# TIDA-010954-ACSwitch.net
KiCad netlist of a schematic drawn in Altium Designer
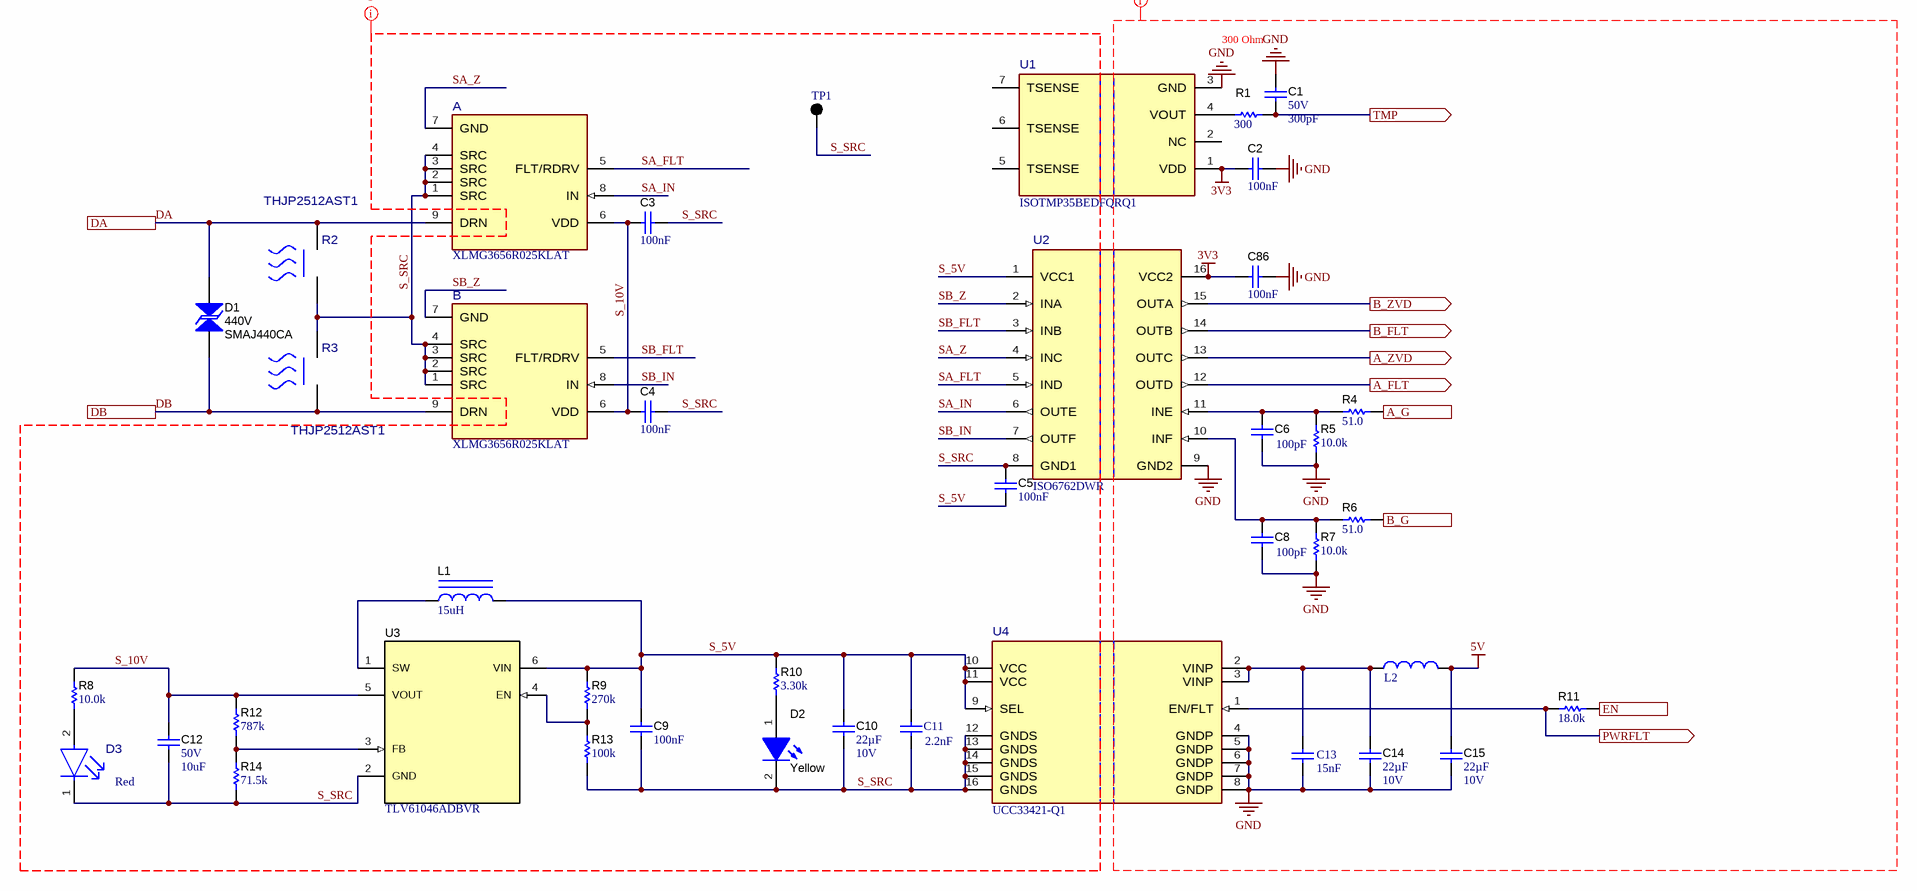
[diagram p0: TIDA-010954-ACSwitch.SchDoc]

(export (version "E")
  (design (tool "Eeschema 10.0.6"))
  (components
    (comp (ref "A")
      (value "XLMG3656R025KLAT")
      (footprint "KLA0009A-MFG")
      (fields
        (field (name "MANUFACTURER") "Texas Instruments")
        (field (name "PARTNUMBER") "XLMG3656R025KLAT")
        (field (name "PART NUMBER") "LMG365x")
      )
      (libsource (lib "Altium Vault - TI") (part "SYM-LMG365x"))
    )
    (comp (ref "B")
      (value "XLMG3656R025KLAT")
      (footprint "KLA0009A-MFG")
      (fields
        (field (name "MANUFACTURER") "Texas Instruments")
        (field (name "PARTNUMBER") "XLMG3656R025KLAT")
        (field (name "PART NUMBER") "LMG365x")
      )
      (libsource (lib "Altium Vault - TI") (part "SYM-LMG365x"))
    )
    (comp (ref "C1")
      (value "GRM1885C1H301JA01D")
      (footprint "0603")
      (description "CAP, CERM, 300 pF, 50 V, +/- 5%, C0G/NP0, 0603")
      (fields
        (field (name "MANUFACTURER") "MuRata")
        (field (name "VDC_V") "50V")
        (field (name "VALUEDISPLAYED") "300pF")
        (field (name "PUBLISHER") "Texas Instruments")
      )
      (libsource (lib "Altium Vault - TI") (part "Capacitor"))
    )
    (comp (ref "C2")
      (value "CGA3E2X7R1E104K080AA")
      (footprint "0603")
      (description "CAP, CERM, 0.1 uF, 25 V, +/- 10%, X7R, AEC-Q200 Grade 1, 0603")
      (fields
        (field (name "MANUFACTURER") "TDK")
        (field (name "CAP_F") "100nF")
        (field (name "PUBLISHER") "Texas Instruments")
      )
      (libsource (lib "Altium Vault - TI") (part "Capacitor"))
    )
    (comp (ref "C3")
      (value "CGA3E2X7R1E104K080AA")
      (footprint "0603")
      (description "CAP, CERM, 0.1 uF, 25 V, +/- 10%, X7R, AEC-Q200 Grade 1, 0603")
      (fields
        (field (name "MANUFACTURER") "TDK")
        (field (name "CAP_F") "100nF")
        (field (name "PUBLISHER") "Texas Instruments")
      )
      (libsource (lib "Altium Vault - TI") (part "Capacitor"))
    )
    (comp (ref "C4")
      (value "CGA3E2X7R1E104K080AA")
      (footprint "0603")
      (description "CAP, CERM, 0.1 uF, 25 V, +/- 10%, X7R, AEC-Q200 Grade 1, 0603")
      (fields
        (field (name "MANUFACTURER") "TDK")
        (field (name "CAP_F") "100nF")
        (field (name "PUBLISHER") "Texas Instruments")
      )
      (libsource (lib "Altium Vault - TI") (part "Capacitor"))
    )
    (comp (ref "C5")
      (value "CGA3E2X7R1E104K080AA")
      (footprint "0603")
      (description "CAP, CERM, 0.1 uF, 25 V, +/- 10%, X7R, AEC-Q200 Grade 1, 0603")
      (fields
        (field (name "MANUFACTURER") "TDK")
        (field (name "CAP_F") "100nF")
        (field (name "PUBLISHER") "Texas Instruments")
      )
      (libsource (lib "Altium Vault - TI") (part "Capacitor"))
    )
    (comp (ref "C6")
      (value "GRM1885C1H101JA01D")
      (footprint "0603")
      (description "CAP, CERM, 100 pF, 50 V, +/- 5%, C0G/NP0, 0603")
      (fields
        (field (name "MANUFACTURER") "MuRata")
        (field (name "VALUEDISPLAYED") "100pF")
        (field (name "PUBLISHER") "Texas Instruments")
      )
      (libsource (lib "Altium Vault - TI") (part "Capacitor"))
    )
    (comp (ref "C8")
      (value "GRM1885C1H101JA01D")
      (footprint "0603")
      (description "CAP, CERM, 100 pF, 50 V, +/- 5%, C0G/NP0, 0603")
      (fields
        (field (name "MANUFACTURER") "MuRata")
        (field (name "VALUEDISPLAYED") "100pF")
        (field (name "PUBLISHER") "Texas Instruments")
      )
      (libsource (lib "Altium Vault - TI") (part "Capacitor"))
    )
    (comp (ref "C9")
      (value "CGA3E2X7R1E104K080AA")
      (footprint "0603")
      (description "CAP, CERM, 0.1 uF, 25 V, +/- 10%, X7R, AEC-Q200 Grade 1, 0603")
      (fields
        (field (name "MANUFACTURER") "TDK")
        (field (name "CAP_F") "100nF")
        (field (name "PUBLISHER") "Texas Instruments")
      )
      (libsource (lib "Altium Vault - TI") (part "Capacitor"))
    )
    (comp (ref "C10")
      (value "GRM21BZ71A226ME15L")
      (footprint "0805_HV")
      (description "CAP, CERM, 22 uF, 10 V, +/- 20%, X7R, 0805")
      (fields
        (field (name "CAP_F") "22µF")
        (field (name "VDC_V") "10V")
        (field (name "MANUFACTURER") "MuRata")
        (field (name "PUBLISHER") "Texas Instruments")
      )
      (libsource (lib "Altium Vault - TI") (part "Capacitor"))
    )
    (comp (ref "C11")
      (value "885012205063")
      (footprint "WCAP-CSGP_0402_L1W0.5H0.5")
      (description "WCAP-CSGP Multilayer Ceramic Chip Capacitor, General Purpose, size 0402, X7R, 2.2nF, 50VDC")
      (fields (field (name "CAP_F") "2.2nF") (field (name "MANUFACTURER") "Wurth Elektronik"))
      (libsource (lib "Altium Vault - TI") (part "8853622110151"))
    )
    (comp (ref "C12")
      (value "GRT31CR61H106KE01L")
      (footprint "1206_180")
      (description "CAP, CERM, 10 uF, 50 V, +/- 10%, X5R, AEC-Q200 Grade 1, 1206")
      (fields
        (field (name "MANUFACTURER") "MuRata")
        (field (name "VDC_V") "50V")
        (field (name "VALUEDISPLAYED") "10uF")
        (field (name "PUBLISHER") "Texas Instruments")
      )
      (libsource (lib "Altium Vault - TI") (part "Capacitor"))
    )
    (comp (ref "C13")
      (value "885012205051")
      (footprint "WCAP-CSGP_0402_L1W0.5H0.5")
      (description "WCAP-CSGP Multilayer Ceramic Chip Capacitor, General Purpose, size 0402, X7R, 15nF, 25VDC")
      (fields (field (name "CAP_F") "15nF") (field (name "MANUFACTURER") "Wurth Elektronik"))
      (libsource (lib "Altium Vault - TI") (part "890764429002CS"))
    )
    (comp (ref "C14")
      (value "GRM21BZ71A226ME15L")
      (footprint "0805_HV")
      (description "CAP, CERM, 22 uF, 10 V, +/- 20%, X7R, 0805")
      (fields
        (field (name "CAP_F") "22µF")
        (field (name "VDC_V") "10V")
        (field (name "MANUFACTURER") "MuRata")
        (field (name "PUBLISHER") "Texas Instruments")
      )
      (libsource (lib "Altium Vault - TI") (part "Capacitor"))
    )
    (comp (ref "C15")
      (value "GRM21BZ71A226ME15L")
      (footprint "0805_HV")
      (description "CAP, CERM, 22 uF, 10 V, +/- 20%, X7R, 0805")
      (fields
        (field (name "CAP_F") "22µF")
        (field (name "VDC_V") "10V")
        (field (name "MANUFACTURER") "MuRata")
        (field (name "PUBLISHER") "Texas Instruments")
      )
      (libsource (lib "Altium Vault - TI") (part "Capacitor"))
    )
    (comp (ref "C86")
      (value "CGA3E2X7R1E104K080AA")
      (footprint "0603")
      (description "CAP, CERM, 0.1 uF, 25 V, +/- 10%, X7R, AEC-Q200 Grade 1, 0603")
      (fields
        (field (name "MANUFACTURER") "TDK")
        (field (name "CAP_F") "100nF")
        (field (name "PUBLISHER") "Texas Instruments")
      )
      (libsource (lib "Altium Vault - TI") (part "Capacitor"))
    )
    (comp (ref "D1")
      (value "SMAJ440CA")
      (footprint "SMA_Bi")
      (description "Diode, TVS, Bi, 440 V, 713 Vc, 400 W, 0.6 A, SMA (non-polarized)")
      (fields (field (name "ALTIUM_VALUE") "440V") (field (name "MANUFACTURER") "Littelfuse"))
      (libsource (lib "Altium Vault - TI") (part "Diode_TVS_Bi"))
    )
    (comp (ref "D2")
      (value "Yellow")
      (footprint "APT1608_Yellow")
      (description "LED, Yellow, SMD")
      (fields (field (name "MANUFACTURER") "Kingbright") (field (name "PARTNUMBER") "APT1608SYCK"))
      (libsource (lib "Altium Vault - TI") (part "LED"))
    )
    (comp (ref "D3")
      (value "APG1608SURKC/T")
      (footprint "FP-APG1608SURKC_T_0603-MFG")
      (description "Red 630nm LED Indication - Discrete 2V 0603 (1608 Metric)")
      (fields
        (field (name "MANUFACTURER") "Kingbright")
        (field (name "MOUSER PART NUMBER") "604-APG1608SURKC/T")
        (field (name "COLOR") "Red")
      )
      (libsource (lib "Altium Vault - TI") (part "SYM-APG1608SURKC_T"))
    )
    (comp (ref "L1")
      (value "SDR0302-150ML")
      (footprint "SDR0302")
      (description "Inductor, Drum Core, Ferrite, 15 uH, 0.65 A, 0.4 ohm, SMD")
      (fields
        (field (name "VALUEDISPLAYED") "15uH")
        (field (name "MANUFACTURER") "Bourns")
        (field (name "PUBLISHER") "Texas Instruments")
      )
      (libsource (lib "Altium Vault - TI") (part "Inductor_Iron"))
    )
    (comp (ref "L2")
      (value "74479763222")
      (footprint "WE-PMI_0603_L1.6W0.8H0.8")
      (description "WE-PMI SMT Power Multilayer Inductor, size 0603, 2.2uH, 0.8A, 375mOhm")
      (fields (field (name "MANUFACTURER") "Wurth Elektronik"))
      (libsource (lib "Altium Vault - TI") (part "74437529203681"))
    )
    (comp (ref "R1")
      (value "RC0603FR-07300RL")
      (footprint "0603")
      (description "RES, 300, 1%, 0.1 W, 0603")
      (fields (field (name "MANUFACTURER") "Yageo") (field (name "VALUEDISPLAYED") "300"))
      (libsource (lib "Altium Vault - TI") (part "Resistor"))
    )
    (comp (ref "R2")
      (value "THJP2512AST1")
      (footprint "FP-THJP2512AST1_2512-MFG")
      (description "Thermal Pad 6.40mm x 3.20mm Rectangular")
      (fields
        (field (name "MANUFACTURER") "Vishay")
        (field (name "DIGIKEY PART NUMBER") "764-THJP2512AST1CT-ND")
      )
      (libsource (lib "Altium Vault - TI") (part "SYM-THJP2512AST1"))
    )
    (comp (ref "R3")
      (value "THJP2512AST1")
      (footprint "FP-THJP2512AST1_2512-MFG")
      (description "Thermal Pad 6.40mm x 3.20mm Rectangular")
      (fields
        (field (name "MANUFACTURER") "Vishay")
        (field (name "DIGIKEY PART NUMBER") "764-THJP2512AST1CT-ND")
      )
      (libsource (lib "Altium Vault - TI") (part "SYM-THJP2512AST1"))
    )
    (comp (ref "R4")
      (value "RC0603FR-0751RL")
      (footprint "0603")
      (description "RES, 51.0, 1%, 0.1 W, 0603")
      (fields (field (name "MANUFACTURER") "Yageo") (field (name "VALUEDISPLAYED") "51.0"))
      (libsource (lib "Altium Vault - TI") (part "Resistor"))
    )
    (comp (ref "R5")
      (value "RC0603FR-0710KL")
      (footprint "0603")
      (description "RES, 10.0 k, 1%, 0.1 W, 0603")
      (fields (field (name "MANUFACTURER") "Yageo") (field (name "VALUEDISPLAYED") "10.0k"))
      (libsource (lib "Altium Vault - TI") (part "Resistor"))
    )
    (comp (ref "R6")
      (value "RC0603FR-0751RL")
      (footprint "0603")
      (description "RES, 51.0, 1%, 0.1 W, 0603")
      (fields (field (name "MANUFACTURER") "Yageo") (field (name "VALUEDISPLAYED") "51.0"))
      (libsource (lib "Altium Vault - TI") (part "Resistor"))
    )
    (comp (ref "R7")
      (value "RC0603FR-0710KL")
      (footprint "0603")
      (description "RES, 10.0 k, 1%, 0.1 W, 0603")
      (fields (field (name "MANUFACTURER") "Yageo") (field (name "VALUEDISPLAYED") "10.0k"))
      (libsource (lib "Altium Vault - TI") (part "Resistor"))
    )
    (comp (ref "R8")
      (value "RC0603FR-0710KL")
      (footprint "0603")
      (description "RES, 10.0 k, 1%, 0.1 W, 0603")
      (fields (field (name "MANUFACTURER") "Yageo") (field (name "VALUEDISPLAYED") "10.0k"))
      (libsource (lib "Altium Vault - TI") (part "Resistor"))
    )
    (comp (ref "R9")
      (value "RC0603FR-07270KL")
      (footprint "0603")
      (description "RES, 270 k, 1%, 0.1 W, 0603")
      (fields (field (name "MANUFACTURER") "Yageo") (field (name "VALUEDISPLAYED") "270k"))
      (libsource (lib "Altium Vault - TI") (part "Resistor"))
    )
    (comp (ref "R10")
      (value "RC0603FR-073K3L")
      (footprint "0603")
      (description "RES, 3.30 k, 1%, 0.1 W, 0603")
      (fields (field (name "VALUEDISPLAYED") "3.30k") (field (name "MANUFACTURER") "Yageo"))
      (libsource (lib "Altium Vault - TI") (part "Resistor"))
    )
    (comp (ref "R11")
      (value "RC0603FR-0718KL")
      (footprint "0603")
      (description "RES, 18.0 k, 1%, 0.1 W, 0603")
      (fields (field (name "MANUFACTURER") "Yageo") (field (name "VALUEDISPLAYED") "18.0k"))
      (libsource (lib "Altium Vault - TI") (part "Resistor"))
    )
    (comp (ref "R12")
      (value "RC0603FR-07787KL")
      (footprint "0603")
      (description "RES, 787 k, 1%, 0.1 W, 0603")
      (fields (field (name "MANUFACTURER") "Yageo") (field (name "VALUEDISPLAYED") "787k"))
      (libsource (lib "Altium Vault - TI") (part "Resistor"))
    )
    (comp (ref "R13")
      (value "RC0603FR-07100KL")
      (footprint "0603")
      (description "RES, 100 k, 1%, 0.1 W, 0603")
      (fields (field (name "MANUFACTURER") "Yageo") (field (name "VALUEDISPLAYED") "100k"))
      (libsource (lib "Altium Vault - TI") (part "Resistor"))
    )
    (comp (ref "R14")
      (value "RC0603FR-0771K5L")
      (footprint "0603")
      (description "RES, 71.5 k, 1%, 0.1 W, 0603")
      (fields (field (name "MANUFACTURER") "Yageo") (field (name "VALUEDISPLAYED") "71.5k"))
      (libsource (lib "Altium Vault - TI") (part "Resistor"))
    )
    (comp (ref "TP1")
      (value "5011")
      (footprint "Keystone5011")
      (description "Test Point, Multipurpose, Black, TH")
      (fields
        (field (name "MANUFACTURER") "Keystone Electronics")
        (field (name "PUBLISHER") "Texas Instruments")
      )
      (libsource (lib "Altium Vault - TI") (part "5011"))
    )
    (comp (ref "U1")
      (value "ISOTMP35BEDFQRQ1")
      (footprint "DFQ0007A-MFG")
      (fields
        (field (name "MANUFACTURER") "Texas Instruments")
        (field (name "PARTNUMBER") "ISOTMP35BEDFQRQ1")
      )
      (libsource (lib "Altium Vault - TI") (part "SYM-ISOTMP35BEDFQRQ1"))
    )
    (comp (ref "U2")
      (value "ISO6762DWR")
      (footprint "DW0016A-MFG")
      (description "General purpose, 50-Mbps, six-channel (4/2) digital isolator 16-SOIC -40 to 125")
      (fields
        (field (name "DIGIKEY PART NUMBER") "296-ISO6762DWRCT-ND")
        (field (name "MANUFACTURER") "Texas Instruments")
        (field (name "PARTNUMBER") "ISO6762DWR")
      )
      (libsource (lib "Altium Vault - TI") (part "SYM-ISO6762DWR"))
    )
    (comp (ref "U3")
      (value "TLV61046ADBVR")
      (footprint "DBV0006A_N")
      (description "28-V Output Voltage Boost Converter with Power Diode and Isolation Switch, DBV0006A (SOT-6)")
      (fields
        (field (name "PARTNUMBER") "TLV61046ADBVR")
        (field (name "MANUFACTURER") "Texas Instruments")
        (field (name "ALTERNATE PARTNUMBER") "TLV61046ADBVT")
        (field (name "PUBLISHER") "Texas Instruments")
      )
      (libsource (lib "Altium Vault - TI") (part "TLV61046"))
    )
    (comp (ref "U4")
      (value "UCC33421-Q1")
      (footprint "DWX0016A-MFG")
      (description "1.5W, High-Density, >5 kVRMS Isolated DC-DC Converter")
      (fields (field (name "MANUFACTURER") "Texas Instruments") (field (name "PARTNUMBER") "UCC33421-Q1"))
      (libsource (lib "Altium Vault - TI") (part "SYM-UCC33421-Q1"))
    )
  )
  (nets
    (net (code "1") (name "/A_FLT") (class "Default")
      (node (ref "U2") (pin "12") (pinfunction "OUTD_12") (pintype "output"))
    )
    (net (code "2") (name "/A_G") (class "Default")
      (node (ref "R4") (pin "2") (pinfunction "2_2") (pintype "passive"))
    )
    (net (code "3") (name "/A_ZVD") (class "Default")
      (node (ref "U2") (pin "13") (pinfunction "OUTC_13") (pintype "output"))
    )
    (net (code "4") (name "/B_FLT") (class "Default")
      (node (ref "U2") (pin "14") (pinfunction "OUTB_14") (pintype "output"))
    )
    (net (code "5") (name "/B_G") (class "Default")
      (node (ref "R6") (pin "2") (pinfunction "2_2") (pintype "passive"))
    )
    (net (code "6") (name "/B_ZVD") (class "Default")
      (node (ref "U2") (pin "15") (pinfunction "OUTA_15") (pintype "output"))
    )
    (net (code "7") (name "/DA") (class "Default")
      (node (ref "A") (pin "9") (pinfunction "DRN_9") (pintype "passive"))
      (node (ref "D1") (pin "2") (pinfunction "2_2") (pintype "passive"))
      (node (ref "R2") (pin "2") (pinfunction "2_2") (pintype "passive"))
    )
    (net (code "8") (name "/DB") (class "Default")
      (node (ref "B") (pin "9") (pinfunction "DRN_9") (pintype "passive"))
      (node (ref "D1") (pin "1") (pinfunction "1_1") (pintype "passive"))
      (node (ref "R3") (pin "1") (pinfunction "1_1") (pintype "passive"))
    )
    (net (code "9") (name "/EN") (class "Default")
      (node (ref "R11") (pin "2") (pinfunction "2_2") (pintype "passive"))
    )
    (net (code "10") (name "/PWRFLT") (class "Default")
      (node (ref "R11") (pin "1") (pinfunction "1_1") (pintype "passive"))
      (node (ref "U4") (pin "1") (pinfunction "EN/FLT_1") (pintype "input"))
    )
    (net (code "11") (name "/SA_FLT") (class "Default")
      (node (ref "A") (pin "5") (pinfunction "FLT/RDRV_5") (pintype "passive"))
      (node (ref "U2") (pin "5") (pinfunction "IND_5") (pintype "input"))
    )
    (net (code "12") (name "/SA_IN") (class "Default")
      (node (ref "A") (pin "8") (pinfunction "IN_8") (pintype "input"))
      (node (ref "U2") (pin "6") (pinfunction "OUTE_6") (pintype "output"))
    )
    (net (code "13") (name "/SA_Z") (class "Default")
      (node (ref "A") (pin "7") (pinfunction "GND_7") (pintype "power_in"))
      (node (ref "U2") (pin "4") (pinfunction "INC_4") (pintype "input"))
    )
    (net (code "14") (name "/SB_FLT") (class "Default")
      (node (ref "B") (pin "5") (pinfunction "FLT/RDRV_5") (pintype "passive"))
      (node (ref "U2") (pin "3") (pinfunction "INB_3") (pintype "input"))
    )
    (net (code "15") (name "/SB_IN") (class "Default")
      (node (ref "B") (pin "8") (pinfunction "IN_8") (pintype "input"))
      (node (ref "U2") (pin "7") (pinfunction "OUTF_7") (pintype "output"))
    )
    (net (code "16") (name "/SB_Z") (class "Default")
      (node (ref "B") (pin "7") (pinfunction "GND_7") (pintype "power_in"))
      (node (ref "U2") (pin "2") (pinfunction "INA_2") (pintype "input"))
    )
    (net (code "17") (name "/S_5V") (class "Default")
      (node (ref "C10") (pin "1") (pinfunction "1_1") (pintype "passive"))
      (node (ref "C11") (pin "2") (pinfunction "2_2") (pintype "passive"))
      (node (ref "C5") (pin "1") (pinfunction "1_1") (pintype "passive"))
      (node (ref "C9") (pin "2") (pinfunction "2_2") (pintype "passive"))
      (node (ref "L1") (pin "2") (pinfunction "2_2") (pintype "passive"))
      (node (ref "R10") (pin "2") (pinfunction "2_2") (pintype "passive"))
      (node (ref "R9") (pin "2") (pinfunction "2_2") (pintype "passive"))
      (node (ref "U2") (pin "1") (pinfunction "VCC1_1") (pintype "power_in"))
      (node (ref "U3") (pin "6") (pinfunction "VIN_6") (pintype "power_in"))
      (node (ref "U4") (pin "10") (pinfunction "VCC_10") (pintype "passive"))
      (node (ref "U4") (pin "11") (pinfunction "VCC_11") (pintype "passive"))
      (node (ref "U4") (pin "9") (pinfunction "SEL_9") (pintype "input"))
    )
    (net (code "18") (name "/S_10V") (class "Default")
      (node (ref "A") (pin "6") (pinfunction "VDD_6") (pintype "power_in"))
      (node (ref "B") (pin "6") (pinfunction "VDD_6") (pintype "power_in"))
      (node (ref "C12") (pin "1") (pinfunction "1_1") (pintype "passive"))
      (node (ref "C3") (pin "1") (pinfunction "1_1") (pintype "passive"))
      (node (ref "C4") (pin "1") (pinfunction "1_1") (pintype "passive"))
      (node (ref "R12") (pin "2") (pinfunction "2_2") (pintype "passive"))
      (node (ref "R8") (pin "2") (pinfunction "2_2") (pintype "passive"))
      (node (ref "U3") (pin "5") (pinfunction "VOUT_5") (pintype "power_in"))
    )
    (net (code "19") (name "/S_SRC") (class "Default")
      (node (ref "A") (pin "1") (pinfunction "SRC_1") (pintype "passive"))
      (node (ref "A") (pin "2") (pinfunction "SRC_2") (pintype "passive"))
      (node (ref "A") (pin "3") (pinfunction "SRC_3") (pintype "passive"))
      (node (ref "A") (pin "4") (pinfunction "SRC_4") (pintype "passive"))
      (node (ref "B") (pin "1") (pinfunction "SRC_1") (pintype "passive"))
      (node (ref "B") (pin "2") (pinfunction "SRC_2") (pintype "passive"))
      (node (ref "B") (pin "3") (pinfunction "SRC_3") (pintype "passive"))
      (node (ref "B") (pin "4") (pinfunction "SRC_4") (pintype "passive"))
      (node (ref "C10") (pin "2") (pinfunction "2_2") (pintype "passive"))
      (node (ref "C11") (pin "1") (pinfunction "1_1") (pintype "passive"))
      (node (ref "C12") (pin "2") (pinfunction "2_2") (pintype "passive"))
      (node (ref "C3") (pin "2") (pinfunction "2_2") (pintype "passive"))
      (node (ref "C4") (pin "2") (pinfunction "2_2") (pintype "passive"))
      (node (ref "C5") (pin "2") (pinfunction "2_2") (pintype "passive"))
      (node (ref "C9") (pin "1") (pinfunction "1_1") (pintype "passive"))
      (node (ref "D2") (pin "2") (pinfunction "K_2") (pintype "passive"))
      (node (ref "D3") (pin "1") (pinfunction "CATHODE_1") (pintype "passive"))
      (node (ref "R13") (pin "1") (pinfunction "1_1") (pintype "passive"))
      (node (ref "R14") (pin "1") (pinfunction "1_1") (pintype "passive"))
      (node (ref "R2") (pin "1") (pinfunction "1_1") (pintype "passive"))
      (node (ref "R3") (pin "2") (pinfunction "2_2") (pintype "passive"))
      (node (ref "TP1") (pin "1") (pintype "passive"))
      (node (ref "U2") (pin "8") (pinfunction "GND1_8") (pintype "power_in"))
      (node (ref "U3") (pin "2") (pinfunction "GND_2") (pintype "power_in"))
      (node (ref "U4") (pin "12") (pinfunction "GNDS_12") (pintype "power_in"))
      (node (ref "U4") (pin "13") (pinfunction "GNDS_13") (pintype "power_in"))
      (node (ref "U4") (pin "14") (pinfunction "GNDS_14") (pintype "power_in"))
      (node (ref "U4") (pin "15") (pinfunction "GNDS_15") (pintype "power_in"))
      (node (ref "U4") (pin "16") (pinfunction "GNDS_16") (pintype "power_in"))
    )
    (net (code "20") (name "/TMP") (class "Default")
      (node (ref "C1") (pin "1") (pinfunction "1_1") (pintype "passive"))
      (node (ref "R1") (pin "2") (pinfunction "2_2") (pintype "passive"))
    )
    (net (code "21") (name "3V3") (class "Default")
      (node (ref "C2") (pin "1") (pinfunction "1_1") (pintype "passive"))
      (node (ref "C86") (pin "1") (pinfunction "1_1") (pintype "passive"))
      (node (ref "U1") (pin "1") (pinfunction "VDD_1") (pintype "power_in"))
      (node (ref "U2") (pin "16") (pinfunction "VCC2_16") (pintype "power_in"))
    )
    (net (code "22") (name "5V") (class "Default")
      (node (ref "C15") (pin "1") (pinfunction "1_1") (pintype "passive"))
      (node (ref "L2") (pin "2") (pinfunction "2_2") (pintype "passive"))
    )
    (net (code "23") (name "GND") (class "Default")
      (node (ref "C1") (pin "2") (pinfunction "2_2") (pintype "passive"))
      (node (ref "C13") (pin "1") (pinfunction "1_1") (pintype "passive"))
      (node (ref "C14") (pin "2") (pinfunction "2_2") (pintype "passive"))
      (node (ref "C15") (pin "2") (pinfunction "2_2") (pintype "passive"))
      (node (ref "C2") (pin "2") (pinfunction "2_2") (pintype "passive"))
      (node (ref "C6") (pin "2") (pinfunction "2_2") (pintype "passive"))
      (node (ref "C8") (pin "2") (pinfunction "2_2") (pintype "passive"))
      (node (ref "C86") (pin "2") (pinfunction "2_2") (pintype "passive"))
      (node (ref "R5") (pin "1") (pinfunction "1_1") (pintype "passive"))
      (node (ref "R7") (pin "1") (pinfunction "1_1") (pintype "passive"))
      (node (ref "U1") (pin "3") (pinfunction "GND_3") (pintype "power_in"))
      (node (ref "U2") (pin "9") (pinfunction "GND2_9") (pintype "power_in"))
      (node (ref "U4") (pin "4") (pinfunction "GNDP_4") (pintype "power_in"))
      (node (ref "U4") (pin "5") (pinfunction "GNDP_5") (pintype "power_in"))
      (node (ref "U4") (pin "6") (pinfunction "GNDP_6") (pintype "power_in"))
      (node (ref "U4") (pin "7") (pinfunction "GNDP_7") (pintype "power_in"))
      (node (ref "U4") (pin "8") (pinfunction "GNDP_8") (pintype "power_in"))
    )
    (net (code "24") (name "Net-(C13-Pad2)") (class "Default")
      (node (ref "C13") (pin "2") (pinfunction "2_2") (pintype "passive"))
      (node (ref "C14") (pin "1") (pinfunction "1_1") (pintype "passive"))
      (node (ref "L2") (pin "1") (pinfunction "1_1") (pintype "passive"))
      (node (ref "U4") (pin "2") (pinfunction "VINP_2") (pintype "power_in"))
      (node (ref "U4") (pin "3") (pinfunction "VINP_3") (pintype "power_in"))
    )
    (net (code "25") (name "Net-(D2-A)") (class "Default")
      (node (ref "D2") (pin "1") (pinfunction "A_1") (pintype "passive"))
      (node (ref "R10") (pin "1") (pinfunction "1_1") (pintype "passive"))
    )
    (net (code "26") (name "Net-(D3-ANODE)") (class "Default")
      (node (ref "D3") (pin "2") (pinfunction "ANODE_2") (pintype "passive"))
      (node (ref "R8") (pin "1") (pinfunction "1_1") (pintype "passive"))
    )
    (net (code "27") (name "Net-(U1-VOUT)") (class "Default")
      (node (ref "R1") (pin "1") (pinfunction "1_1") (pintype "passive"))
      (node (ref "U1") (pin "4") (pinfunction "VOUT_4") (pintype "passive"))
    )
    (net (code "28") (name "Net-(U2-INE)") (class "Default")
      (node (ref "C6") (pin "1") (pinfunction "1_1") (pintype "passive"))
      (node (ref "R4") (pin "1") (pinfunction "1_1") (pintype "passive"))
      (node (ref "R5") (pin "2") (pinfunction "2_2") (pintype "passive"))
      (node (ref "U2") (pin "11") (pinfunction "INE_11") (pintype "input"))
    )
    (net (code "29") (name "Net-(U2-INF)") (class "Default")
      (node (ref "C8") (pin "1") (pinfunction "1_1") (pintype "passive"))
      (node (ref "R6") (pin "1") (pinfunction "1_1") (pintype "passive"))
      (node (ref "R7") (pin "2") (pinfunction "2_2") (pintype "passive"))
      (node (ref "U2") (pin "10") (pinfunction "INF_10") (pintype "input"))
    )
    (net (code "30") (name "Net-(U3-EN)") (class "Default")
      (node (ref "R13") (pin "2") (pinfunction "2_2") (pintype "passive"))
      (node (ref "R9") (pin "1") (pinfunction "1_1") (pintype "passive"))
      (node (ref "U3") (pin "4") (pinfunction "EN_4") (pintype "input"))
    )
    (net (code "31") (name "Net-(U3-FB)") (class "Default")
      (node (ref "R12") (pin "1") (pinfunction "1_1") (pintype "passive"))
      (node (ref "R14") (pin "2") (pinfunction "2_2") (pintype "passive"))
      (node (ref "U3") (pin "3") (pinfunction "FB_3") (pintype "input"))
    )
    (net (code "32") (name "Net-(U3-SW)") (class "Default")
      (node (ref "L1") (pin "1") (pinfunction "1_1") (pintype "passive"))
      (node (ref "U3") (pin "1") (pinfunction "SW_1") (pintype "power_in"))
    )
    (net (code "33") (name "unconnected-(U1-NC-Pad2)") (class "Default")
      (node (ref "U1") (pin "2") (pinfunction "NC_2") (pintype "passive"))
    )
    (net (code "34") (name "unconnected-(U1-TSENSE-Pad5)") (class "Default")
      (node (ref "U1") (pin "5") (pinfunction "TSENSE_5") (pintype "passive"))
    )
    (net (code "35") (name "unconnected-(U1-TSENSE-Pad6)") (class "Default")
      (node (ref "U1") (pin "6") (pinfunction "TSENSE_6") (pintype "passive"))
    )
    (net (code "36") (name "unconnected-(U1-TSENSE-Pad7)") (class "Default")
      (node (ref "U1") (pin "7") (pinfunction "TSENSE_7") (pintype "passive"))
    )
  )
)
